# power_indicator_left.net
KiCad netlist of a schematic drawn in EAGLE
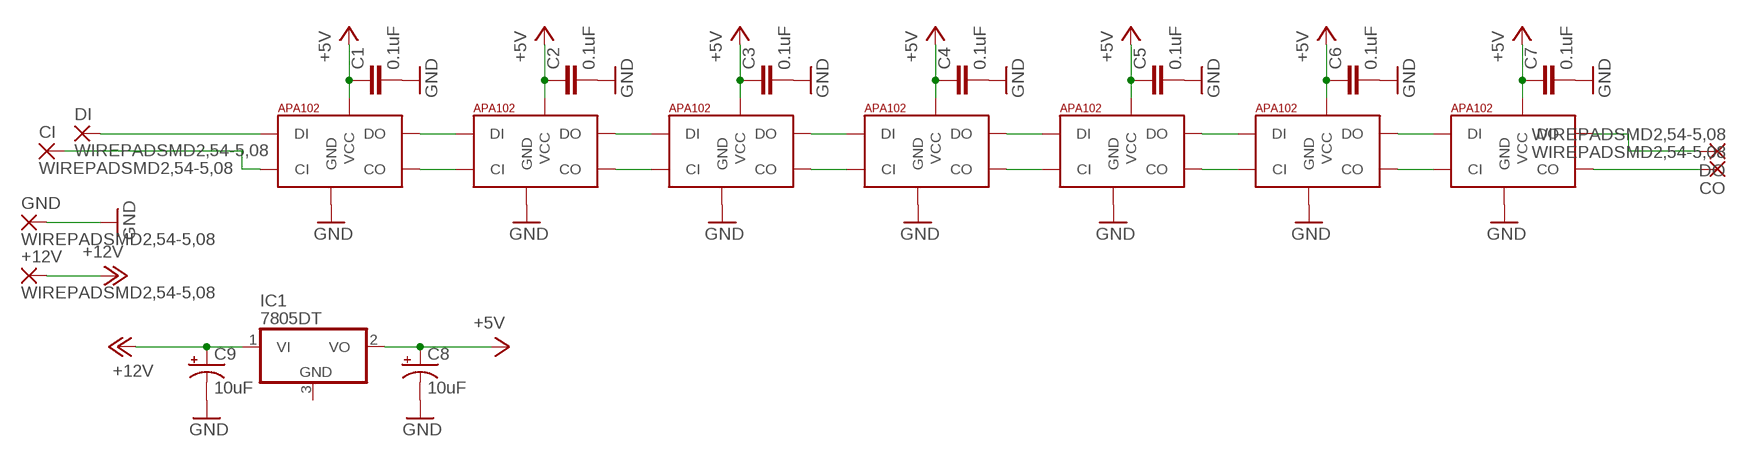
[diagram p0: schematic, sheet 1]

(export (version "E")
  (design (tool "Eeschema 10.0.6"))
  (components
    (comp (ref "+12V")
      (value "WIREPADSMD2,54-5,08")
      (footprint "eagle-import:SMD2,54-5,08")
      (libsource (lib "eagle-import") (part "WIREPADSMD2,54-5,08"))
    )
    (comp (ref "C1")
      (value "0.1uF")
      (footprint "eagle-import:0603-CAP")
      (libsource (lib "eagle-import") (part "0.1UF-100V-10%(0603)"))
    )
    (comp (ref "C2")
      (value "0.1uF")
      (footprint "eagle-import:0603-CAP")
      (libsource (lib "eagle-import") (part "0.1UF-100V-10%(0603)"))
    )
    (comp (ref "C3")
      (value "0.1uF")
      (footprint "eagle-import:0603-CAP")
      (libsource (lib "eagle-import") (part "0.1UF-100V-10%(0603)"))
    )
    (comp (ref "C4")
      (value "0.1uF")
      (footprint "eagle-import:0603-CAP")
      (libsource (lib "eagle-import") (part "0.1UF-100V-10%(0603)"))
    )
    (comp (ref "C5")
      (value "0.1uF")
      (footprint "eagle-import:0603-CAP")
      (libsource (lib "eagle-import") (part "0.1UF-100V-10%(0603)"))
    )
    (comp (ref "C6")
      (value "0.1uF")
      (footprint "eagle-import:0603-CAP")
      (libsource (lib "eagle-import") (part "0.1UF-100V-10%(0603)"))
    )
    (comp (ref "C7")
      (value "0.1uF")
      (footprint "eagle-import:0603-CAP")
      (libsource (lib "eagle-import") (part "0.1UF-100V-10%(0603)"))
    )
    (comp (ref "C8")
      (value "10uF")
      (footprint "eagle-import:EIA3216")
      (libsource (lib "eagle-import") (part "10UF-TANT"))
    )
    (comp (ref "C9")
      (value "10uF")
      (footprint "eagle-import:EIA3216")
      (libsource (lib "eagle-import") (part "10UF-TANT"))
    )
    (comp (ref "CI")
      (value "WIREPADSMD2,54-5,08")
      (footprint "eagle-import:SMD2,54-5,08")
      (libsource (lib "eagle-import") (part "WIREPADSMD2,54-5,08"))
    )
    (comp (ref "CO")
      (value "WIREPADSMD2,54-5,08")
      (footprint "eagle-import:SMD2,54-5,08")
      (libsource (lib "eagle-import") (part "WIREPADSMD2,54-5,08"))
    )
    (comp (ref "DI")
      (value "WIREPADSMD2,54-5,08")
      (footprint "eagle-import:SMD2,54-5,08")
      (libsource (lib "eagle-import") (part "WIREPADSMD2,54-5,08"))
    )
    (comp (ref "DO")
      (value "WIREPADSMD2,54-5,08")
      (footprint "eagle-import:SMD2,54-5,08")
      (libsource (lib "eagle-import") (part "WIREPADSMD2,54-5,08"))
    )
    (comp (ref "GND")
      (value "WIREPADSMD2,54-5,08")
      (footprint "eagle-import:SMD2,54-5,08")
      (libsource (lib "eagle-import") (part "WIREPADSMD2,54-5,08"))
    )
    (comp (ref "IC1")
      (value "7805DT")
      (footprint "eagle-import:TO252")
      (libsource (lib "eagle-import") (part "78DT05"))
    )
    (comp (ref "U$1")
      (value "APA1025050")
      (footprint "eagle-import:APA102_5050")
      (libsource (lib "eagle-import") (part "APA1025050"))
    )
    (comp (ref "U$2")
      (value "APA1025050")
      (footprint "eagle-import:APA102_5050")
      (libsource (lib "eagle-import") (part "APA1025050"))
    )
    (comp (ref "U$3")
      (value "APA1025050")
      (footprint "eagle-import:APA102_5050")
      (libsource (lib "eagle-import") (part "APA1025050"))
    )
    (comp (ref "U$4")
      (value "APA1025050")
      (footprint "eagle-import:APA102_5050")
      (libsource (lib "eagle-import") (part "APA1025050"))
    )
    (comp (ref "U$5")
      (value "APA1025050")
      (footprint "eagle-import:APA102_5050")
      (libsource (lib "eagle-import") (part "APA1025050"))
    )
    (comp (ref "U$6")
      (value "APA1025050")
      (footprint "eagle-import:APA102_5050")
      (libsource (lib "eagle-import") (part "APA1025050"))
    )
    (comp (ref "U$7")
      (value "APA1025050")
      (footprint "eagle-import:APA102_5050")
      (libsource (lib "eagle-import") (part "APA1025050"))
    )
  )
  (nets
    (net (code "1") (name "+5V") (class "Default")
      (node (ref "C1") (pin "1") (pinfunction "1_1") (pintype "passive"))
      (node (ref "C2") (pin "1") (pinfunction "1_1") (pintype "passive"))
      (node (ref "C3") (pin "1") (pinfunction "1_1") (pintype "passive"))
      (node (ref "C4") (pin "1") (pinfunction "1_1") (pintype "passive"))
      (node (ref "C5") (pin "1") (pinfunction "1_1") (pintype "passive"))
      (node (ref "C6") (pin "1") (pinfunction "1_1") (pintype "passive"))
      (node (ref "C7") (pin "1") (pinfunction "1_1") (pintype "passive"))
      (node (ref "C8") (pin "A") (pinfunction "+_A") (pintype "passive"))
      (node (ref "IC1") (pin "2") (pinfunction "VO_2") (pintype "passive"))
      (node (ref "U$1") (pin "1") (pinfunction "VCC_1") (pintype "bidirectional"))
      (node (ref "U$2") (pin "1") (pinfunction "VCC_1") (pintype "bidirectional"))
      (node (ref "U$3") (pin "1") (pinfunction "VCC_1") (pintype "bidirectional"))
      (node (ref "U$4") (pin "1") (pinfunction "VCC_1") (pintype "bidirectional"))
      (node (ref "U$5") (pin "1") (pinfunction "VCC_1") (pintype "bidirectional"))
      (node (ref "U$6") (pin "1") (pinfunction "VCC_1") (pintype "bidirectional"))
      (node (ref "U$7") (pin "1") (pinfunction "VCC_1") (pintype "bidirectional"))
    )
    (net (code "2") (name "+12V") (class "Default")
      (node (ref "+12V") (pin "1") (pinfunction "P_1") (pintype "passive"))
      (node (ref "C9") (pin "A") (pinfunction "+_A") (pintype "passive"))
      (node (ref "IC1") (pin "1") (pinfunction "VI_1") (pintype "input"))
    )
    (net (code "3") (name "GND") (class "Default")
      (node (ref "C1") (pin "2") (pinfunction "2_2") (pintype "passive"))
      (node (ref "C2") (pin "2") (pinfunction "2_2") (pintype "passive"))
      (node (ref "C3") (pin "2") (pinfunction "2_2") (pintype "passive"))
      (node (ref "C4") (pin "2") (pinfunction "2_2") (pintype "passive"))
      (node (ref "C5") (pin "2") (pinfunction "2_2") (pintype "passive"))
      (node (ref "C6") (pin "2") (pinfunction "2_2") (pintype "passive"))
      (node (ref "C7") (pin "2") (pinfunction "2_2") (pintype "passive"))
      (node (ref "C8") (pin "C") (pinfunction "-_C") (pintype "passive"))
      (node (ref "C9") (pin "C") (pinfunction "-_C") (pintype "passive"))
      (node (ref "GND") (pin "1") (pinfunction "P_1") (pintype "passive"))
      (node (ref "U$1") (pin "6") (pinfunction "GND_6") (pintype "bidirectional"))
      (node (ref "U$2") (pin "6") (pinfunction "GND_6") (pintype "bidirectional"))
      (node (ref "U$3") (pin "6") (pinfunction "GND_6") (pintype "bidirectional"))
      (node (ref "U$4") (pin "6") (pinfunction "GND_6") (pintype "bidirectional"))
      (node (ref "U$5") (pin "6") (pinfunction "GND_6") (pintype "bidirectional"))
      (node (ref "U$6") (pin "6") (pinfunction "GND_6") (pintype "bidirectional"))
      (node (ref "U$7") (pin "6") (pinfunction "GND_6") (pintype "bidirectional"))
    )
    (net (code "4") (name "Net-(CI-P)") (class "Default")
      (node (ref "CI") (pin "1") (pinfunction "P_1") (pintype "passive"))
      (node (ref "U$1") (pin "5") (pinfunction "CI_5") (pintype "bidirectional"))
    )
    (net (code "5") (name "Net-(CO-P)") (class "Default")
      (node (ref "CO") (pin "1") (pinfunction "P_1") (pintype "passive"))
      (node (ref "U$7") (pin "2") (pinfunction "CO_2") (pintype "bidirectional"))
    )
    (net (code "6") (name "Net-(DI-P)") (class "Default")
      (node (ref "DI") (pin "1") (pinfunction "P_1") (pintype "passive"))
      (node (ref "U$1") (pin "4") (pinfunction "DI_4") (pintype "bidirectional"))
    )
    (net (code "7") (name "Net-(DO-P)") (class "Default")
      (node (ref "DO") (pin "1") (pinfunction "P_1") (pintype "passive"))
      (node (ref "U$7") (pin "3") (pinfunction "DO_3") (pintype "bidirectional"))
    )
    (net (code "8") (name "Net-(U$1-CO)") (class "Default")
      (node (ref "U$1") (pin "2") (pinfunction "CO_2") (pintype "bidirectional"))
      (node (ref "U$2") (pin "5") (pinfunction "CI_5") (pintype "bidirectional"))
    )
    (net (code "9") (name "Net-(U$1-DO)") (class "Default")
      (node (ref "U$1") (pin "3") (pinfunction "DO_3") (pintype "bidirectional"))
      (node (ref "U$2") (pin "4") (pinfunction "DI_4") (pintype "bidirectional"))
    )
    (net (code "10") (name "Net-(U$2-CO)") (class "Default")
      (node (ref "U$2") (pin "2") (pinfunction "CO_2") (pintype "bidirectional"))
      (node (ref "U$3") (pin "5") (pinfunction "CI_5") (pintype "bidirectional"))
    )
    (net (code "11") (name "Net-(U$2-DO)") (class "Default")
      (node (ref "U$2") (pin "3") (pinfunction "DO_3") (pintype "bidirectional"))
      (node (ref "U$3") (pin "4") (pinfunction "DI_4") (pintype "bidirectional"))
    )
    (net (code "12") (name "Net-(U$3-CO)") (class "Default")
      (node (ref "U$3") (pin "2") (pinfunction "CO_2") (pintype "bidirectional"))
      (node (ref "U$4") (pin "5") (pinfunction "CI_5") (pintype "bidirectional"))
    )
    (net (code "13") (name "Net-(U$3-DO)") (class "Default")
      (node (ref "U$3") (pin "3") (pinfunction "DO_3") (pintype "bidirectional"))
      (node (ref "U$4") (pin "4") (pinfunction "DI_4") (pintype "bidirectional"))
    )
    (net (code "14") (name "Net-(U$4-CO)") (class "Default")
      (node (ref "U$4") (pin "2") (pinfunction "CO_2") (pintype "bidirectional"))
      (node (ref "U$5") (pin "5") (pinfunction "CI_5") (pintype "bidirectional"))
    )
    (net (code "15") (name "Net-(U$4-DO)") (class "Default")
      (node (ref "U$4") (pin "3") (pinfunction "DO_3") (pintype "bidirectional"))
      (node (ref "U$5") (pin "4") (pinfunction "DI_4") (pintype "bidirectional"))
    )
    (net (code "16") (name "Net-(U$5-CO)") (class "Default")
      (node (ref "U$5") (pin "2") (pinfunction "CO_2") (pintype "bidirectional"))
      (node (ref "U$6") (pin "5") (pinfunction "CI_5") (pintype "bidirectional"))
    )
    (net (code "17") (name "Net-(U$5-DO)") (class "Default")
      (node (ref "U$5") (pin "3") (pinfunction "DO_3") (pintype "bidirectional"))
      (node (ref "U$6") (pin "4") (pinfunction "DI_4") (pintype "bidirectional"))
    )
    (net (code "18") (name "Net-(U$6-CO)") (class "Default")
      (node (ref "U$6") (pin "2") (pinfunction "CO_2") (pintype "bidirectional"))
      (node (ref "U$7") (pin "5") (pinfunction "CI_5") (pintype "bidirectional"))
    )
    (net (code "19") (name "Net-(U$6-DO)") (class "Default")
      (node (ref "U$6") (pin "3") (pinfunction "DO_3") (pintype "bidirectional"))
      (node (ref "U$7") (pin "4") (pinfunction "DI_4") (pintype "bidirectional"))
    )
    (net (code "20") (name "unconnected-(IC1-GND-Pad3)") (class "Default")
      (node (ref "IC1") (pin "3") (pinfunction "GND_3") (pintype "passive"))
    )
  )
)
